# lononTV.net
KiCad netlist of a schematic drawn in Altium Designer
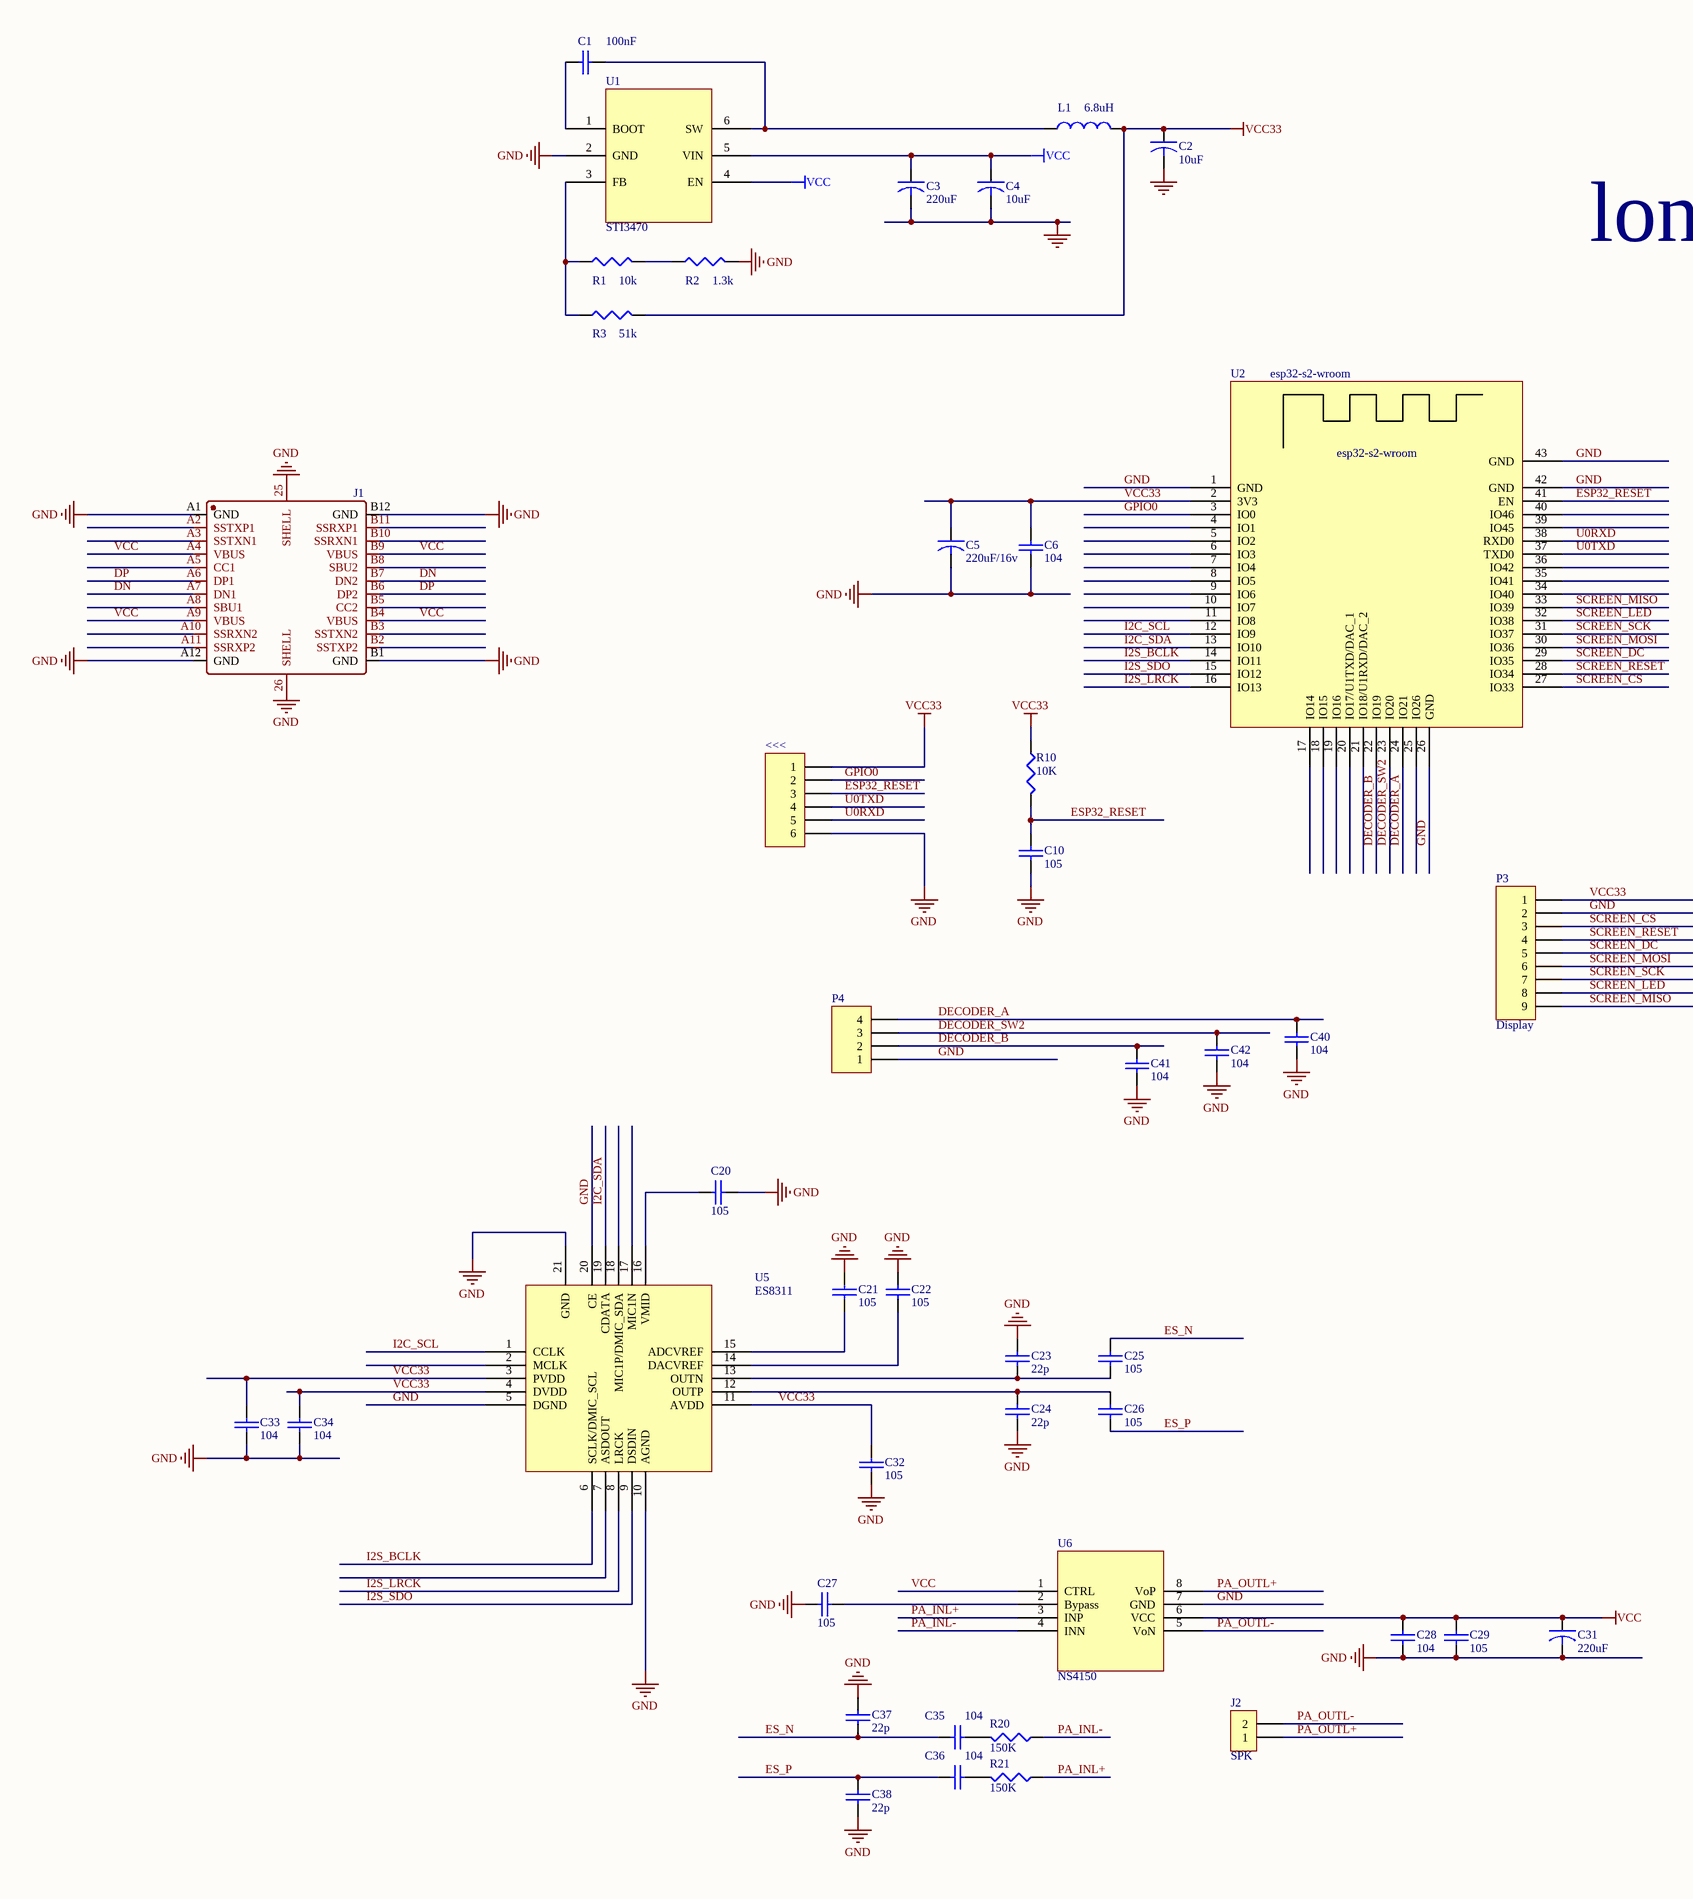
[diagram p0: lononTV.SchDoc, left]
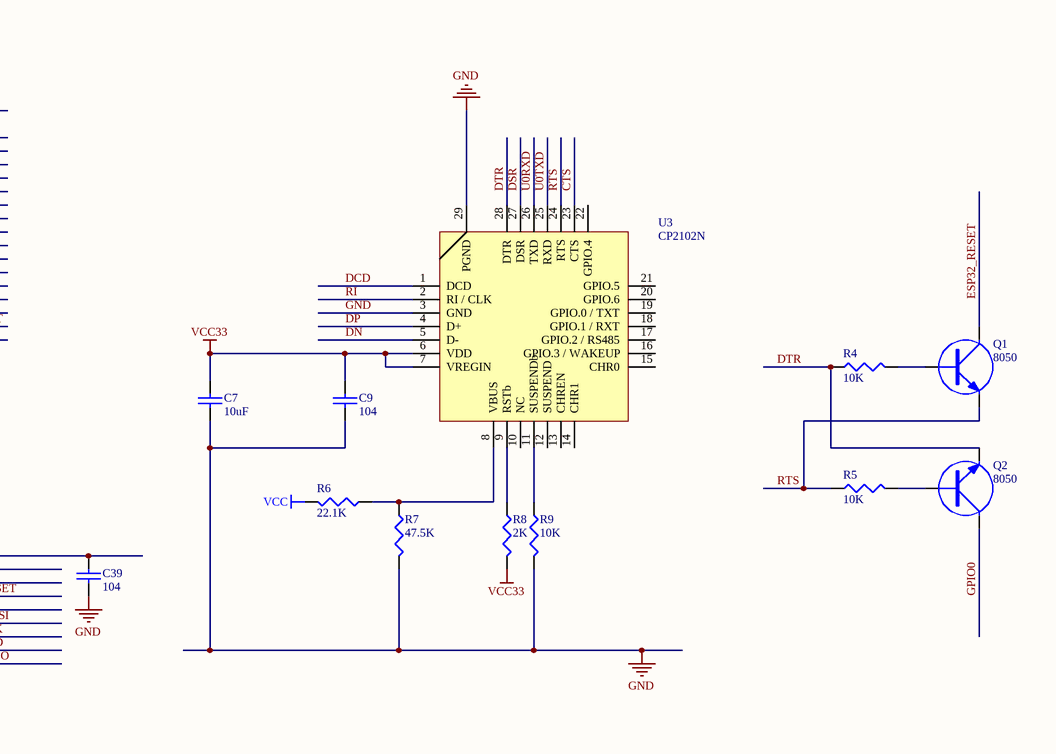
[diagram p1: lononTV.SchDoc, right]

(export (version "E")
  (design (tool "Eeschema 10.0.6"))
  (components
    (comp (ref "<<<")
      (value "~")
      (footprint "6PIN_2.0")
      (description "Header, 6-Pin")
      (fields (field (name "PUBLISHER") "Altium Limited"))
      (libsource (lib "Miscellaneous Connectors") (part "Header 6"))
    )
    (comp (ref "C1")
      (value "100nF")
      (footprint "0603C")
      (description "贴片电容")
      (libsource (lib "*") (part "CAP"))
    )
    (comp (ref "C2")
      (value "10uF")
      (footprint "1206-A")
      (description "钽电容")
      (libsource (lib "*") (part "CAPACITOR"))
    )
    (comp (ref "C3")
      (value "220uF")
      (footprint "铝电容6.6")
      (description "钽电容")
      (libsource (lib "*") (part "CAPACITOR"))
    )
    (comp (ref "C4")
      (value "10uF")
      (footprint "1206-A")
      (description "钽电容")
      (libsource (lib "*") (part "CAPACITOR"))
    )
    (comp (ref "C5")
      (value "220uF/16v")
      (footprint "铝电容6.6")
      (description "Capacitor")
      (libsource (lib "zhjrm") (part "CAPACITOR"))
    )
    (comp (ref "C6")
      (value "104")
      (footprint "C0603 - duplicate")
      (description "Capacitor")
      (libsource (lib "zhjrm") (part "CAP"))
    )
    (comp (ref "C7")
      (value "10uF")
      (footprint "1206-A")
      (description "Capacitor")
      (libsource (lib "zhjrm") (part "CAP"))
    )
    (comp (ref "C9")
      (value "104")
      (footprint "C0603 - duplicate")
      (description "Capacitor")
      (libsource (lib "zhjrm") (part "CAP"))
    )
    (comp (ref "C10")
      (value "105")
      (footprint "C0603 - duplicate")
      (description "Capacitor")
      (libsource (lib "zhjrm") (part "CAP"))
    )
    (comp (ref "C20")
      (value "105")
      (footprint "C0603 - duplicate")
      (description "Capacitor")
      (libsource (lib "zhjrm") (part "CAP"))
    )
    (comp (ref "C21")
      (value "105")
      (footprint "C0603 - duplicate")
      (description "Capacitor")
      (libsource (lib "zhjrm") (part "CAP"))
    )
    (comp (ref "C22")
      (value "105")
      (footprint "C0603 - duplicate")
      (description "Capacitor")
      (libsource (lib "zhjrm") (part "CAP"))
    )
    (comp (ref "C23")
      (value "22p")
      (footprint "C0603 - duplicate")
      (description "Capacitor")
      (libsource (lib "zhjrm") (part "CAP"))
    )
    (comp (ref "C24")
      (value "22p")
      (footprint "C0603 - duplicate")
      (description "Capacitor")
      (libsource (lib "zhjrm") (part "CAP"))
    )
    (comp (ref "C25")
      (value "105")
      (footprint "C0603 - duplicate")
      (description "Capacitor")
      (libsource (lib "zhjrm") (part "CAP"))
    )
    (comp (ref "C26")
      (value "105")
      (footprint "C0603 - duplicate")
      (description "Capacitor")
      (libsource (lib "zhjrm") (part "CAP"))
    )
    (comp (ref "C27")
      (value "105")
      (footprint "C0603 - duplicate")
      (description "Capacitor")
      (libsource (lib "zhjrm") (part "CAP"))
    )
    (comp (ref "C28")
      (value "104")
      (footprint "C0603 - duplicate")
      (description "Capacitor")
      (libsource (lib "zhjrm") (part "CAP"))
    )
    (comp (ref "C29")
      (value "105")
      (footprint "C0603 - duplicate")
      (description "Capacitor")
      (libsource (lib "zhjrm") (part "CAP"))
    )
    (comp (ref "C31")
      (value "220uF")
      (footprint "铝电容6.6")
      (description "Capacitor")
      (libsource (lib "zhjrm") (part "CAPACITOR"))
    )
    (comp (ref "C32")
      (value "105")
      (footprint "C0603 - duplicate")
      (description "Capacitor")
      (libsource (lib "zhjrm") (part "CAP"))
    )
    (comp (ref "C33")
      (value "104")
      (footprint "C0603 - duplicate")
      (description "Capacitor")
      (libsource (lib "zhjrm") (part "CAP"))
    )
    (comp (ref "C34")
      (value "104")
      (footprint "C0603 - duplicate")
      (description "Capacitor")
      (libsource (lib "zhjrm") (part "CAP"))
    )
    (comp (ref "C35")
      (value "104")
      (footprint "C0603 - duplicate")
      (description "Capacitor")
      (libsource (lib "zhjrm") (part "CAP"))
    )
    (comp (ref "C36")
      (value "104")
      (footprint "C0603 - duplicate")
      (description "Capacitor")
      (libsource (lib "zhjrm") (part "CAP"))
    )
    (comp (ref "C37")
      (value "22p")
      (footprint "C0603 - duplicate")
      (description "Capacitor")
      (libsource (lib "zhjrm") (part "CAP"))
    )
    (comp (ref "C38")
      (value "22p")
      (footprint "C0603 - duplicate")
      (description "Capacitor")
      (libsource (lib "zhjrm") (part "CAP"))
    )
    (comp (ref "C39")
      (value "104")
      (footprint "C0603 - duplicate")
      (description "Capacitor")
      (libsource (lib "zhjrm") (part "CAP"))
    )
    (comp (ref "C40")
      (value "104")
      (footprint "C0603 - duplicate")
      (description "Capacitor")
      (libsource (lib "zhjrm") (part "CAP"))
    )
    (comp (ref "C41")
      (value "104")
      (footprint "C0603 - duplicate")
      (description "Capacitor")
      (libsource (lib "zhjrm") (part "CAP"))
    )
    (comp (ref "C42")
      (value "104")
      (footprint "C0603 - duplicate")
      (description "Capacitor")
      (libsource (lib "zhjrm") (part "CAP"))
    )
    (comp (ref "J1")
      (value "~")
      (footprint "TYPE-C夹板C2856664")
      (libsource (lib "zhjrm") (part "TYPE-C夹板C2856664"))
    )
    (comp (ref "J2") (value "SPK") (footprint "PH2.0-2P SMT 立") (libsource (lib "zhjrm") (part "CON2")))
    (comp (ref "L1")
      (value "6.8uH")
      (footprint "电感7.4*6.6")
      (description "Inductor")
      (fields
        (field (name "MANUFACTURER") "Generic Components")
        (field (name "PUBLISHER") "Altium Hobart Technology Centre")
      )
      (libsource (lib "zhjrm") (part "Inductor"))
    )
    (comp (ref "P3")
      (value "Display")
      (footprint "HDR1X9")
      (description "Header, 9-Pin")
      (fields (field (name "PUBLISHER") "Altium Limited"))
      (libsource (lib "Miscellaneous Connectors") (part "Header 9"))
    )
    (comp (ref "P4")
      (value "Header 4")
      (footprint "MX1.25-4P 卧")
      (description "Header, 4-Pin")
      (fields (field (name "PUBLISHER") "Altium Limited"))
      (libsource (lib "Miscellaneous Connectors") (part "Header 4"))
    )
    (comp (ref "Q1")
      (value "8050")
      (footprint "3904")
      (description "NPN Transistor")
      (libsource (lib "zhjrm") (part "NPN"))
    )
    (comp (ref "Q2")
      (value "8050")
      (footprint "3904")
      (description "NPN Transistor")
      (libsource (lib "zhjrm") (part "NPN"))
    )
    (comp (ref "R1") (value "10k") (footprint "0603R") (libsource (lib "*") (part "RES1")))
    (comp (ref "R2") (value "1.3k") (footprint "0603R") (libsource (lib "*") (part "RES1")))
    (comp (ref "R3") (value "51k") (footprint "0603R") (libsource (lib "*") (part "RES1")))
    (comp (ref "R4") (value "10K") (footprint "R0603") (libsource (lib "zhjrm") (part "RES1")))
    (comp (ref "R5") (value "10K") (footprint "R0603") (libsource (lib "zhjrm") (part "RES1")))
    (comp (ref "R6") (value "22.1K") (footprint "R0603") (libsource (lib "zhjrm") (part "RES1")))
    (comp (ref "R7") (value "47.5K") (footprint "R0603") (libsource (lib "zhjrm") (part "RES1")))
    (comp (ref "R8") (value "2K") (footprint "R0603") (libsource (lib "zhjrm") (part "RES1")))
    (comp (ref "R9") (value "10K") (footprint "R0603") (libsource (lib "zhjrm") (part "RES1")))
    (comp (ref "R10") (value "10K") (footprint "0603R") (libsource (lib "zhjrm") (part "RES1")))
    (comp (ref "R20") (value "150K") (footprint "0603R") (libsource (lib "zhjrm") (part "RES1")))
    (comp (ref "R21") (value "150K") (footprint "0603R") (libsource (lib "zhjrm") (part "RES1")))
    (comp (ref "U1") (value "STI3470") (footprint "SOT-23-6L") (libsource (lib "zhjrm") (part "RT7285/A")))
    (comp (ref "U2")
      (value "esp32-s2-wroom")
      (footprint "ESP32-S2-WROOM")
      (libsource (lib "zhjrm") (part "esp32-s2-wroom"))
    )
    (comp (ref "U3")
      (value "CP2102N")
      (footprint "QFN 28-pin-05P")
      (libsource (lib "zhjrm") (part "CP2102N"))
    )
    (comp (ref "U5") (value "ES8311") (footprint "QFN20_3*3") (libsource (lib "zhjrm") (part "ES8311")))
    (comp (ref "U6") (value "NS4150") (footprint "MSOP8") (libsource (lib "zhjrm") (part "NS4150")))
  )
  (nets
    (net (code "1") (name "/CTS") (class "Default")
      (node (ref "U3") (pin "23") (pinfunction "CTS_23") (pintype "passive"))
    )
    (net (code "2") (name "/DCD") (class "Default")
      (node (ref "U3") (pin "1") (pinfunction "DCD_1") (pintype "passive"))
    )
    (net (code "3") (name "/DECODER_A") (class "Default")
      (node (ref "C40") (pin "1") (pinfunction "1_1") (pintype "passive"))
      (node (ref "P4") (pin "4") (pinfunction "4_4") (pintype "passive"))
      (node (ref "U2") (pin "24") (pinfunction "IO21_24") (pintype "passive"))
    )
    (net (code "4") (name "/DECODER_B") (class "Default")
      (node (ref "C41") (pin "1") (pinfunction "1_1") (pintype "passive"))
      (node (ref "P4") (pin "2") (pinfunction "2_2") (pintype "passive"))
      (node (ref "U2") (pin "22") (pinfunction "IO19_22") (pintype "passive"))
    )
    (net (code "5") (name "/DECODER_SW2") (class "Default")
      (node (ref "C42") (pin "1") (pinfunction "1_1") (pintype "passive"))
      (node (ref "P4") (pin "3") (pinfunction "3_3") (pintype "passive"))
      (node (ref "U2") (pin "23") (pinfunction "IO20_23") (pintype "passive"))
    )
    (net (code "6") (name "/DN") (class "Default")
      (node (ref "J1") (pin "A7") (pinfunction "DN1_A7") (pintype "passive"))
      (node (ref "J1") (pin "B7") (pinfunction "DN2_B7") (pintype "passive"))
      (node (ref "U3") (pin "5") (pinfunction "D-_5") (pintype "passive"))
    )
    (net (code "7") (name "/DP") (class "Default")
      (node (ref "J1") (pin "A6") (pinfunction "DP1_A6") (pintype "passive"))
      (node (ref "J1") (pin "B6") (pinfunction "DP2_B6") (pintype "passive"))
      (node (ref "U3") (pin "4") (pinfunction "D+_4") (pintype "passive"))
    )
    (net (code "8") (name "/DSR") (class "Default")
      (node (ref "U3") (pin "27") (pinfunction "DSR_27") (pintype "passive"))
    )
    (net (code "9") (name "/DTR") (class "Default")
      (node (ref "Q2") (pin "3") (pinfunction "E_3") (pintype "passive"))
      (node (ref "R4") (pin "1") (pinfunction "1_1") (pintype "passive"))
      (node (ref "U3") (pin "28") (pinfunction "DTR_28") (pintype "passive"))
    )
    (net (code "10") (name "/ESP32_RESET") (class "Default")
      (node (ref "<<<") (pin "3") (pinfunction "3_3") (pintype "passive"))
      (node (ref "C10") (pin "1") (pinfunction "1_1") (pintype "passive"))
      (node (ref "Q1") (pin "2") (pinfunction "C_2") (pintype "passive"))
      (node (ref "R10") (pin "2") (pinfunction "2_2") (pintype "passive"))
      (node (ref "U2") (pin "41") (pinfunction "EN_41") (pintype "passive"))
    )
    (net (code "11") (name "/ES_N") (class "Default")
      (node (ref "C25") (pin "1") (pinfunction "1_1") (pintype "passive"))
      (node (ref "C35") (pin "2") (pinfunction "2_2") (pintype "passive"))
      (node (ref "C37") (pin "2") (pinfunction "2_2") (pintype "passive"))
    )
    (net (code "12") (name "/ES_P") (class "Default")
      (node (ref "C26") (pin "2") (pinfunction "2_2") (pintype "passive"))
      (node (ref "C36") (pin "2") (pinfunction "2_2") (pintype "passive"))
      (node (ref "C38") (pin "1") (pinfunction "1_1") (pintype "passive"))
    )
    (net (code "13") (name "/GPIO0") (class "Default")
      (node (ref "<<<") (pin "2") (pinfunction "2_2") (pintype "passive"))
      (node (ref "Q2") (pin "2") (pinfunction "C_2") (pintype "passive"))
      (node (ref "U2") (pin "3") (pinfunction "IO0_3") (pintype "passive"))
    )
    (net (code "14") (name "/I2C_SCL") (class "Default")
      (node (ref "U2") (pin "12") (pinfunction "IO9_12") (pintype "passive"))
      (node (ref "U5") (pin "1") (pinfunction "CCLK_1") (pintype "passive"))
    )
    (net (code "15") (name "/I2C_SDA") (class "Default")
      (node (ref "U2") (pin "13") (pinfunction "IO10_13") (pintype "passive"))
      (node (ref "U5") (pin "19") (pinfunction "CDATA_19") (pintype "passive"))
    )
    (net (code "16") (name "/I2S_BCLK") (class "Default")
      (node (ref "U2") (pin "14") (pinfunction "IO11_14") (pintype "passive"))
      (node (ref "U5") (pin "6") (pinfunction "SCLK/DMIC_SCL_6") (pintype "passive"))
    )
    (net (code "17") (name "/I2S_LRCK") (class "Default")
      (node (ref "U2") (pin "16") (pinfunction "IO13_16") (pintype "passive"))
      (node (ref "U5") (pin "8") (pinfunction "LRCK_8") (pintype "passive"))
    )
    (net (code "18") (name "/I2S_SDO") (class "Default")
      (node (ref "U2") (pin "15") (pinfunction "IO12_15") (pintype "passive"))
      (node (ref "U5") (pin "9") (pinfunction "DSDIN_9") (pintype "passive"))
    )
    (net (code "19") (name "/PA_INL+") (class "Default")
      (node (ref "R21") (pin "1") (pinfunction "1_1") (pintype "passive"))
      (node (ref "U6") (pin "3") (pinfunction "INP_3") (pintype "passive"))
    )
    (net (code "20") (name "/PA_INL-") (class "Default")
      (node (ref "R20") (pin "1") (pinfunction "1_1") (pintype "passive"))
      (node (ref "U6") (pin "4") (pinfunction "INN_4") (pintype "passive"))
    )
    (net (code "21") (name "/PA_OUTL+") (class "Default")
      (node (ref "J2") (pin "1") (pinfunction "1_1") (pintype "passive"))
      (node (ref "U6") (pin "8") (pinfunction "VoP_8") (pintype "passive"))
    )
    (net (code "22") (name "/PA_OUTL-") (class "Default")
      (node (ref "J2") (pin "2") (pinfunction "2_2") (pintype "passive"))
      (node (ref "U6") (pin "5") (pinfunction "VoN_5") (pintype "passive"))
    )
    (net (code "23") (name "/RI") (class "Default")
      (node (ref "U3") (pin "2") (pinfunction "RI_/_CLK_2") (pintype "passive"))
    )
    (net (code "24") (name "/RTS") (class "Default")
      (node (ref "Q1") (pin "3") (pinfunction "E_3") (pintype "passive"))
      (node (ref "R5") (pin "1") (pinfunction "1_1") (pintype "passive"))
      (node (ref "U3") (pin "24") (pinfunction "RTS_24") (pintype "passive"))
    )
    (net (code "25") (name "/SCREEN_CS") (class "Default")
      (node (ref "P3") (pin "3") (pinfunction "3_3") (pintype "passive"))
      (node (ref "U2") (pin "27") (pinfunction "IO33_27") (pintype "passive"))
    )
    (net (code "26") (name "/SCREEN_DC") (class "Default")
      (node (ref "P3") (pin "5") (pinfunction "5_5") (pintype "passive"))
      (node (ref "U2") (pin "29") (pinfunction "IO35_29") (pintype "passive"))
    )
    (net (code "27") (name "/SCREEN_LED") (class "Default")
      (node (ref "P3") (pin "8") (pinfunction "8_8") (pintype "passive"))
      (node (ref "U2") (pin "32") (pinfunction "IO38_32") (pintype "passive"))
    )
    (net (code "28") (name "/SCREEN_MISO") (class "Default")
      (node (ref "P3") (pin "9") (pinfunction "9_9") (pintype "passive"))
      (node (ref "U2") (pin "33") (pinfunction "IO39_33") (pintype "passive"))
    )
    (net (code "29") (name "/SCREEN_MOSI") (class "Default")
      (node (ref "P3") (pin "6") (pinfunction "6_6") (pintype "passive"))
      (node (ref "U2") (pin "30") (pinfunction "IO36_30") (pintype "passive"))
    )
    (net (code "30") (name "/SCREEN_RESET") (class "Default")
      (node (ref "P3") (pin "4") (pinfunction "4_4") (pintype "passive"))
      (node (ref "U2") (pin "28") (pinfunction "IO34_28") (pintype "passive"))
    )
    (net (code "31") (name "/SCREEN_SCK") (class "Default")
      (node (ref "P3") (pin "7") (pinfunction "7_7") (pintype "passive"))
      (node (ref "U2") (pin "31") (pinfunction "IO37_31") (pintype "passive"))
    )
    (net (code "32") (name "/U0RXD") (class "Default")
      (node (ref "<<<") (pin "5") (pinfunction "5_5") (pintype "passive"))
      (node (ref "U2") (pin "38") (pinfunction "RXD0_38") (pintype "passive"))
      (node (ref "U3") (pin "26") (pinfunction "TXD_26") (pintype "passive"))
    )
    (net (code "33") (name "/U0TXD") (class "Default")
      (node (ref "<<<") (pin "4") (pinfunction "4_4") (pintype "passive"))
      (node (ref "U2") (pin "37") (pinfunction "TXD0_37") (pintype "passive"))
      (node (ref "U3") (pin "25") (pinfunction "RXD_25") (pintype "passive"))
    )
    (net (code "34") (name "GND") (class "Default")
      (node (ref "<<<") (pin "6") (pinfunction "6_6") (pintype "passive"))
      (node (ref "C10") (pin "2") (pinfunction "2_2") (pintype "passive"))
      (node (ref "C2") (pin "2") (pinfunction "2_2") (pintype "passive"))
      (node (ref "C20") (pin "2") (pinfunction "2_2") (pintype "passive"))
      (node (ref "C21") (pin "2") (pinfunction "2_2") (pintype "passive"))
      (node (ref "C22") (pin "2") (pinfunction "2_2") (pintype "passive"))
      (node (ref "C23") (pin "1") (pinfunction "1_1") (pintype "passive"))
      (node (ref "C24") (pin "2") (pinfunction "2_2") (pintype "passive"))
      (node (ref "C27") (pin "1") (pinfunction "1_1") (pintype "passive"))
      (node (ref "C28") (pin "1") (pinfunction "1_1") (pintype "passive"))
      (node (ref "C29") (pin "1") (pinfunction "1_1") (pintype "passive"))
      (node (ref "C3") (pin "2") (pinfunction "2_2") (pintype "passive"))
      (node (ref "C31") (pin "2") (pinfunction "2_2") (pintype "passive"))
      (node (ref "C32") (pin "1") (pinfunction "1_1") (pintype "passive"))
      (node (ref "C33") (pin "1") (pinfunction "1_1") (pintype "passive"))
      (node (ref "C34") (pin "1") (pinfunction "1_1") (pintype "passive"))
      (node (ref "C37") (pin "1") (pinfunction "1_1") (pintype "passive"))
      (node (ref "C38") (pin "2") (pinfunction "2_2") (pintype "passive"))
      (node (ref "C39") (pin "2") (pinfunction "2_2") (pintype "passive"))
      (node (ref "C4") (pin "2") (pinfunction "2_2") (pintype "passive"))
      (node (ref "C40") (pin "2") (pinfunction "2_2") (pintype "passive"))
      (node (ref "C41") (pin "2") (pinfunction "2_2") (pintype "passive"))
      (node (ref "C42") (pin "2") (pinfunction "2_2") (pintype "passive"))
      (node (ref "C5") (pin "2") (pinfunction "2_2") (pintype "passive"))
      (node (ref "C6") (pin "2") (pinfunction "2_2") (pintype "passive"))
      (node (ref "C7") (pin "2") (pinfunction "2_2") (pintype "passive"))
      (node (ref "C9") (pin "2") (pinfunction "2_2") (pintype "passive"))
      (node (ref "J1") (pin "25") (pinfunction "SHELL_25") (pintype "passive"))
      (node (ref "J1") (pin "26") (pinfunction "SHELL_26") (pintype "passive"))
      (node (ref "J1") (pin "A1") (pinfunction "GND_A1") (pintype "passive"))
      (node (ref "J1") (pin "A12") (pinfunction "GND_A12") (pintype "passive"))
      (node (ref "J1") (pin "B1") (pinfunction "GND_B1") (pintype "passive"))
      (node (ref "J1") (pin "B12") (pinfunction "GND_B12") (pintype "passive"))
      (node (ref "P3") (pin "2") (pinfunction "2_2") (pintype "passive"))
      (node (ref "P4") (pin "1") (pinfunction "1_1") (pintype "passive"))
      (node (ref "R2") (pin "1") (pinfunction "1_1") (pintype "passive"))
      (node (ref "R7") (pin "2") (pinfunction "2_2") (pintype "passive"))
      (node (ref "R9") (pin "2") (pinfunction "2_2") (pintype "passive"))
      (node (ref "U1") (pin "2") (pinfunction "GND_2") (pintype "passive"))
      (node (ref "U2") (pin "1") (pinfunction "GND_1") (pintype "passive"))
      (node (ref "U2") (pin "26") (pinfunction "GND_26") (pintype "passive"))
      (node (ref "U2") (pin "42") (pinfunction "GND_42") (pintype "passive"))
      (node (ref "U2") (pin "43") (pinfunction "GND_43") (pintype "passive"))
      (node (ref "U3") (pin "29") (pinfunction "PGND_29") (pintype "passive"))
      (node (ref "U3") (pin "3") (pinfunction "GND_3") (pintype "passive"))
      (node (ref "U5") (pin "10") (pinfunction "AGND_10") (pintype "passive"))
      (node (ref "U5") (pin "20") (pinfunction "CE_20") (pintype "passive"))
      (node (ref "U5") (pin "21") (pinfunction "GND_21") (pintype "passive"))
      (node (ref "U5") (pin "5") (pinfunction "DGND_5") (pintype "passive"))
      (node (ref "U6") (pin "7") (pinfunction "GND_7") (pintype "passive"))
    )
    (net (code "35") (name "Net-(C35-Pad1)") (class "Default")
      (node (ref "C35") (pin "1") (pinfunction "1_1") (pintype "passive"))
      (node (ref "R20") (pin "2") (pinfunction "2_2") (pintype "passive"))
    )
    (net (code "36") (name "Net-(C36-Pad1)") (class "Default")
      (node (ref "C36") (pin "1") (pinfunction "1_1") (pintype "passive"))
      (node (ref "R21") (pin "2") (pinfunction "2_2") (pintype "passive"))
    )
    (net (code "37") (name "Net-(Q1-B)") (class "Default")
      (node (ref "Q1") (pin "1") (pinfunction "B_1") (pintype "passive"))
      (node (ref "R4") (pin "2") (pinfunction "2_2") (pintype "passive"))
    )
    (net (code "38") (name "Net-(Q2-B)") (class "Default")
      (node (ref "Q2") (pin "1") (pinfunction "B_1") (pintype "passive"))
      (node (ref "R5") (pin "2") (pinfunction "2_2") (pintype "passive"))
    )
    (net (code "39") (name "Net-(R1-Pad1)") (class "Default")
      (node (ref "R1") (pin "1") (pinfunction "1_1") (pintype "passive"))
      (node (ref "R2") (pin "2") (pinfunction "2_2") (pintype "passive"))
    )
    (net (code "40") (name "Net-(U1-BOOT)") (class "Default")
      (node (ref "C1") (pin "1") (pinfunction "1_1") (pintype "passive"))
      (node (ref "U1") (pin "1") (pinfunction "BOOT_1") (pintype "passive"))
    )
    (net (code "41") (name "Net-(U1-FB)") (class "Default")
      (node (ref "R1") (pin "2") (pinfunction "2_2") (pintype "passive"))
      (node (ref "R3") (pin "2") (pinfunction "2_2") (pintype "passive"))
      (node (ref "U1") (pin "3") (pinfunction "FB_3") (pintype "passive"))
    )
    (net (code "42") (name "Net-(U1-SW)") (class "Default")
      (node (ref "C1") (pin "2") (pinfunction "2_2") (pintype "passive"))
      (node (ref "L1") (pin "1") (pinfunction "1_1") (pintype "passive"))
      (node (ref "U1") (pin "6") (pinfunction "SW_6") (pintype "passive"))
    )
    (net (code "43") (name "Net-(U3-RSTb)") (class "Default")
      (node (ref "R8") (pin "1") (pinfunction "1_1") (pintype "passive"))
      (node (ref "U3") (pin "9") (pinfunction "RSTb_9") (pintype "passive"))
    )
    (net (code "44") (name "Net-(U3-SUSPENDb)") (class "Default")
      (node (ref "R9") (pin "1") (pinfunction "1_1") (pintype "passive"))
      (node (ref "U3") (pin "11") (pinfunction "SUSPENDb_11") (pintype "passive"))
    )
    (net (code "45") (name "Net-(U3-VBUS)") (class "Default")
      (node (ref "R6") (pin "1") (pinfunction "1_1") (pintype "passive"))
      (node (ref "R7") (pin "1") (pinfunction "1_1") (pintype "passive"))
      (node (ref "U3") (pin "8") (pinfunction "VBUS_8") (pintype "passive"))
    )
    (net (code "46") (name "Net-(U5-ADCVREF)") (class "Default")
      (node (ref "C21") (pin "1") (pinfunction "1_1") (pintype "passive"))
      (node (ref "U5") (pin "15") (pinfunction "ADCVREF_15") (pintype "passive"))
    )
    (net (code "47") (name "Net-(U5-DACVREF)") (class "Default")
      (node (ref "C22") (pin "1") (pinfunction "1_1") (pintype "passive"))
      (node (ref "U5") (pin "14") (pinfunction "DACVREF_14") (pintype "passive"))
    )
    (net (code "48") (name "Net-(U5-OUTN)") (class "Default")
      (node (ref "C23") (pin "2") (pinfunction "2_2") (pintype "passive"))
      (node (ref "C25") (pin "2") (pinfunction "2_2") (pintype "passive"))
      (node (ref "U5") (pin "13") (pinfunction "OUTN_13") (pintype "passive"))
    )
    (net (code "49") (name "Net-(U5-OUTP)") (class "Default")
      (node (ref "C24") (pin "1") (pinfunction "1_1") (pintype "passive"))
      (node (ref "C26") (pin "1") (pinfunction "1_1") (pintype "passive"))
      (node (ref "U5") (pin "12") (pinfunction "OUTP_12") (pintype "passive"))
    )
    (net (code "50") (name "Net-(U5-VMID)") (class "Default")
      (node (ref "C20") (pin "1") (pinfunction "1_1") (pintype "passive"))
      (node (ref "U5") (pin "16") (pinfunction "VMID_16") (pintype "passive"))
    )
    (net (code "51") (name "Net-(U6-Bypass)") (class "Default")
      (node (ref "C27") (pin "2") (pinfunction "2_2") (pintype "passive"))
      (node (ref "U6") (pin "2") (pinfunction "Bypass_2") (pintype "passive"))
    )
    (net (code "52") (name "VCC") (class "Default")
      (node (ref "C28") (pin "2") (pinfunction "2_2") (pintype "passive"))
      (node (ref "C29") (pin "2") (pinfunction "2_2") (pintype "passive"))
      (node (ref "C3") (pin "1") (pinfunction "1_1") (pintype "passive"))
      (node (ref "C31") (pin "1") (pinfunction "1_1") (pintype "passive"))
      (node (ref "C4") (pin "1") (pinfunction "1_1") (pintype "passive"))
      (node (ref "J1") (pin "A4") (pinfunction "VBUS_A4") (pintype "passive"))
      (node (ref "J1") (pin "A9") (pinfunction "VBUS_A9") (pintype "passive"))
      (node (ref "J1") (pin "B4") (pinfunction "VBUS_B4") (pintype "passive"))
      (node (ref "J1") (pin "B9") (pinfunction "VBUS_B9") (pintype "passive"))
      (node (ref "R6") (pin "2") (pinfunction "2_2") (pintype "passive"))
      (node (ref "U1") (pin "4") (pinfunction "EN_4") (pintype "passive"))
      (node (ref "U1") (pin "5") (pinfunction "VIN_5") (pintype "passive"))
      (node (ref "U6") (pin "1") (pinfunction "CTRL_1") (pintype "passive"))
      (node (ref "U6") (pin "6") (pinfunction "VCC_6") (pintype "passive"))
    )
    (net (code "53") (name "VCC33") (class "Default")
      (node (ref "<<<") (pin "1") (pinfunction "1_1") (pintype "passive"))
      (node (ref "C2") (pin "1") (pinfunction "1_1") (pintype "passive"))
      (node (ref "C32") (pin "2") (pinfunction "2_2") (pintype "passive"))
      (node (ref "C33") (pin "2") (pinfunction "2_2") (pintype "passive"))
      (node (ref "C34") (pin "2") (pinfunction "2_2") (pintype "passive"))
      (node (ref "C39") (pin "1") (pinfunction "1_1") (pintype "passive"))
      (node (ref "C5") (pin "1") (pinfunction "1_1") (pintype "passive"))
      (node (ref "C6") (pin "1") (pinfunction "1_1") (pintype "passive"))
      (node (ref "C7") (pin "1") (pinfunction "1_1") (pintype "passive"))
      (node (ref "C9") (pin "1") (pinfunction "1_1") (pintype "passive"))
      (node (ref "L1") (pin "2") (pinfunction "2_2") (pintype "passive"))
      (node (ref "P3") (pin "1") (pinfunction "1_1") (pintype "passive"))
      (node (ref "R10") (pin "1") (pinfunction "1_1") (pintype "passive"))
      (node (ref "R3") (pin "1") (pinfunction "1_1") (pintype "passive"))
      (node (ref "R8") (pin "2") (pinfunction "2_2") (pintype "passive"))
      (node (ref "U2") (pin "2") (pinfunction "3V3_2") (pintype "passive"))
      (node (ref "U3") (pin "6") (pinfunction "VDD_6") (pintype "passive"))
      (node (ref "U3") (pin "7") (pinfunction "VREGIN_7") (pintype "passive"))
      (node (ref "U5") (pin "11") (pinfunction "AVDD_11") (pintype "passive"))
      (node (ref "U5") (pin "3") (pinfunction "PVDD_3") (pintype "passive"))
      (node (ref "U5") (pin "4") (pinfunction "DVDD_4") (pintype "passive"))
    )
    (net (code "54") (name "unconnected-(J1-CC1-PadA5)") (class "Default")
      (node (ref "J1") (pin "A5") (pinfunction "CC1_A5") (pintype "passive"))
    )
    (net (code "55") (name "unconnected-(J1-CC2-PadB5)") (class "Default")
      (node (ref "J1") (pin "B5") (pinfunction "CC2_B5") (pintype "passive"))
    )
    (net (code "56") (name "unconnected-(J1-SBU1-PadA8)") (class "Default")
      (node (ref "J1") (pin "A8") (pinfunction "SBU1_A8") (pintype "passive"))
    )
    (net (code "57") (name "unconnected-(J1-SBU2-PadB8)") (class "Default")
      (node (ref "J1") (pin "B8") (pinfunction "SBU2_B8") (pintype "passive"))
    )
    (net (code "58") (name "unconnected-(J1-SSRXN1-PadB10)") (class "Default")
      (node (ref "J1") (pin "B10") (pinfunction "SSRXN1_B10") (pintype "passive"))
    )
    (net (code "59") (name "unconnected-(J1-SSRXN2-PadA10)") (class "Default")
      (node (ref "J1") (pin "A10") (pinfunction "SSRXN2_A10") (pintype "passive"))
    )
    (net (code "60") (name "unconnected-(J1-SSRXP1-PadB11)") (class "Default")
      (node (ref "J1") (pin "B11") (pinfunction "SSRXP1_B11") (pintype "passive"))
    )
    (net (code "61") (name "unconnected-(J1-SSRXP2-PadA11)") (class "Default")
      (node (ref "J1") (pin "A11") (pinfunction "SSRXP2_A11") (pintype "passive"))
    )
    (net (code "62") (name "unconnected-(J1-SSTXN1-PadA3)") (class "Default")
      (node (ref "J1") (pin "A3") (pinfunction "SSTXN1_A3") (pintype "passive"))
    )
    (net (code "63") (name "unconnected-(J1-SSTXN2-PadB3)") (class "Default")
      (node (ref "J1") (pin "B3") (pinfunction "SSTXN2_B3") (pintype "passive"))
    )
    (net (code "64") (name "unconnected-(J1-SSTXP1-PadA2)") (class "Default")
      (node (ref "J1") (pin "A2") (pinfunction "SSTXP1_A2") (pintype "passive"))
    )
    (net (code "65") (name "unconnected-(J1-SSTXP2-PadB2)") (class "Default")
      (node (ref "J1") (pin "B2") (pinfunction "SSTXP2_B2") (pintype "passive"))
    )
    (net (code "66") (name "unconnected-(U2-IO1-Pad4)") (class "Default")
      (node (ref "U2") (pin "4") (pinfunction "IO1_4") (pintype "passive"))
    )
    (net (code "67") (name "unconnected-(U2-IO2-Pad5)") (class "Default")
      (node (ref "U2") (pin "5") (pinfunction "IO2_5") (pintype "passive"))
    )
    (net (code "68") (name "unconnected-(U2-IO3-Pad6)") (class "Default")
      (node (ref "U2") (pin "6") (pinfunction "IO3_6") (pintype "passive"))
    )
    (net (code "69") (name "unconnected-(U2-IO4-Pad7)") (class "Default")
      (node (ref "U2") (pin "7") (pinfunction "IO4_7") (pintype "passive"))
    )
    (net (code "70") (name "unconnected-(U2-IO5-Pad8)") (class "Default")
      (node (ref "U2") (pin "8") (pinfunction "IO5_8") (pintype "passive"))
    )
    (net (code "71") (name "unconnected-(U2-IO6-Pad9)") (class "Default")
      (node (ref "U2") (pin "9") (pinfunction "IO6_9") (pintype "passive"))
    )
    (net (code "72") (name "unconnected-(U2-IO7-Pad10)") (class "Default")
      (node (ref "U2") (pin "10") (pinfunction "IO7_10") (pintype "passive"))
    )
    (net (code "73") (name "unconnected-(U2-IO8-Pad11)") (class "Default")
      (node (ref "U2") (pin "11") (pinfunction "IO8_11") (pintype "passive"))
    )
    (net (code "74") (name "unconnected-(U2-IO14-Pad17)") (class "Default")
      (node (ref "U2") (pin "17") (pinfunction "IO14_17") (pintype "passive"))
    )
    (net (code "75") (name "unconnected-(U2-IO15-Pad18)") (class "Default")
      (node (ref "U2") (pin "18") (pinfunction "IO15_18") (pintype "passive"))
    )
    (net (code "76") (name "unconnected-(U2-IO16-Pad19)") (class "Default")
      (node (ref "U2") (pin "19") (pinfunction "IO16_19") (pintype "passive"))
    )
    (net (code "77") (name "unconnected-(U2-IO17{slash}U1TXD{slash}DAC_1-Pad20)") (class "Default")
      (node (ref "U2") (pin "20") (pinfunction "IO17/U1TXD/DAC_1_20") (pintype "passive"))
    )
    (net (code "78") (name "unconnected-(U2-IO18{slash}U1RXD{slash}DAC_2-Pad21)") (class "Default")
      (node (ref "U2") (pin "21") (pinfunction "IO18/U1RXD/DAC_2_21") (pintype "passive"))
    )
    (net (code "79") (name "unconnected-(U2-IO26-Pad25)") (class "Default")
      (node (ref "U2") (pin "25") (pinfunction "IO26_25") (pintype "passive"))
    )
    (net (code "80") (name "unconnected-(U2-IO40-Pad34)") (class "Default")
      (node (ref "U2") (pin "34") (pinfunction "IO40_34") (pintype "passive"))
    )
    (net (code "81") (name "unconnected-(U2-IO41-Pad35)") (class "Default")
      (node (ref "U2") (pin "35") (pinfunction "IO41_35") (pintype "passive"))
    )
    (net (code "82") (name "unconnected-(U2-IO42-Pad36)") (class "Default")
      (node (ref "U2") (pin "36") (pinfunction "IO42_36") (pintype "passive"))
    )
    (net (code "83") (name "unconnected-(U2-IO45-Pad39)") (class "Default")
      (node (ref "U2") (pin "39") (pinfunction "IO45_39") (pintype "passive"))
    )
    (net (code "84") (name "unconnected-(U2-IO46-Pad40)") (class "Default")
      (node (ref "U2") (pin "40") (pinfunction "IO46_40") (pintype "passive"))
    )
    (net (code "85") (name "unconnected-(U3-CHR0-Pad15)") (class "Default")
      (node (ref "U3") (pin "15") (pinfunction "CHR0_15") (pintype "passive"))
    )
    (net (code "86") (name "unconnected-(U3-CHR1-Pad14)") (class "Default")
      (node (ref "U3") (pin "14") (pinfunction "CHR1_14") (pintype "passive"))
    )
    (net (code "87") (name "unconnected-(U3-CHREN-Pad13)") (class "Default")
      (node (ref "U3") (pin "13") (pinfunction "CHREN_13") (pintype "passive"))
    )
    (net (code "88") (name "unconnected-(U3-GPIO.0_{slash}_TXT-Pad19)") (class "Default")
      (node (ref "U3") (pin "19") (pinfunction "GPIO.0_/_TXT_19") (pintype "passive"))
    )
    (net (code "89") (name "unconnected-(U3-GPIO.1_{slash}_RXT-Pad18)") (class "Default")
      (node (ref "U3") (pin "18") (pinfunction "GPIO.1_/_RXT_18") (pintype "passive"))
    )
    (net (code "90") (name "unconnected-(U3-GPIO.2_{slash}_RS485-Pad17)") (class "Default")
      (node (ref "U3") (pin "17") (pinfunction "GPIO.2_/_RS485_17") (pintype "passive"))
    )
    (net (code "91") (name "unconnected-(U3-GPIO.3_{slash}_WAKEUP-Pad16)") (class "Default")
      (node (ref "U3") (pin "16") (pinfunction "GPIO.3_/_WAKEUP_16") (pintype "passive"))
    )
    (net (code "92") (name "unconnected-(U3-GPIO.4-Pad22)") (class "Default")
      (node (ref "U3") (pin "22") (pinfunction "GPIO.4_22") (pintype "passive"))
    )
    (net (code "93") (name "unconnected-(U3-GPIO.5-Pad21)") (class "Default")
      (node (ref "U3") (pin "21") (pinfunction "GPIO.5_21") (pintype "passive"))
    )
    (net (code "94") (name "unconnected-(U3-GPIO.6-Pad20)") (class "Default")
      (node (ref "U3") (pin "20") (pinfunction "GPIO.6_20") (pintype "passive"))
    )
    (net (code "95") (name "unconnected-(U3-NC-Pad10)") (class "Default")
      (node (ref "U3") (pin "10") (pinfunction "NC_10") (pintype "passive"))
    )
    (net (code "96") (name "unconnected-(U3-SUSPEND-Pad12)") (class "Default")
      (node (ref "U3") (pin "12") (pinfunction "SUSPEND_12") (pintype "passive"))
    )
    (net (code "97") (name "unconnected-(U5-ASDOUT-Pad7)") (class "Default")
      (node (ref "U5") (pin "7") (pinfunction "ASDOUT_7") (pintype "passive"))
    )
    (net (code "98") (name "unconnected-(U5-MCLK-Pad2)") (class "Default")
      (node (ref "U5") (pin "2") (pinfunction "MCLK_2") (pintype "passive"))
    )
    (net (code "99") (name "unconnected-(U5-MIC1N-Pad17)") (class "Default")
      (node (ref "U5") (pin "17") (pinfunction "MIC1N_17") (pintype "passive"))
    )
    (net (code "100") (name "unconnected-(U5-MIC1P{slash}DMIC_SDA-Pad18)") (class "Default")
      (node (ref "U5") (pin "18") (pinfunction "MIC1P/DMIC_SDA_18") (pintype "passive"))
    )
  )
)
